# FMC_HPC_UFL_DEBUG_J85_J156.net
KiCad netlist of a schematic drawn in Altium Designer
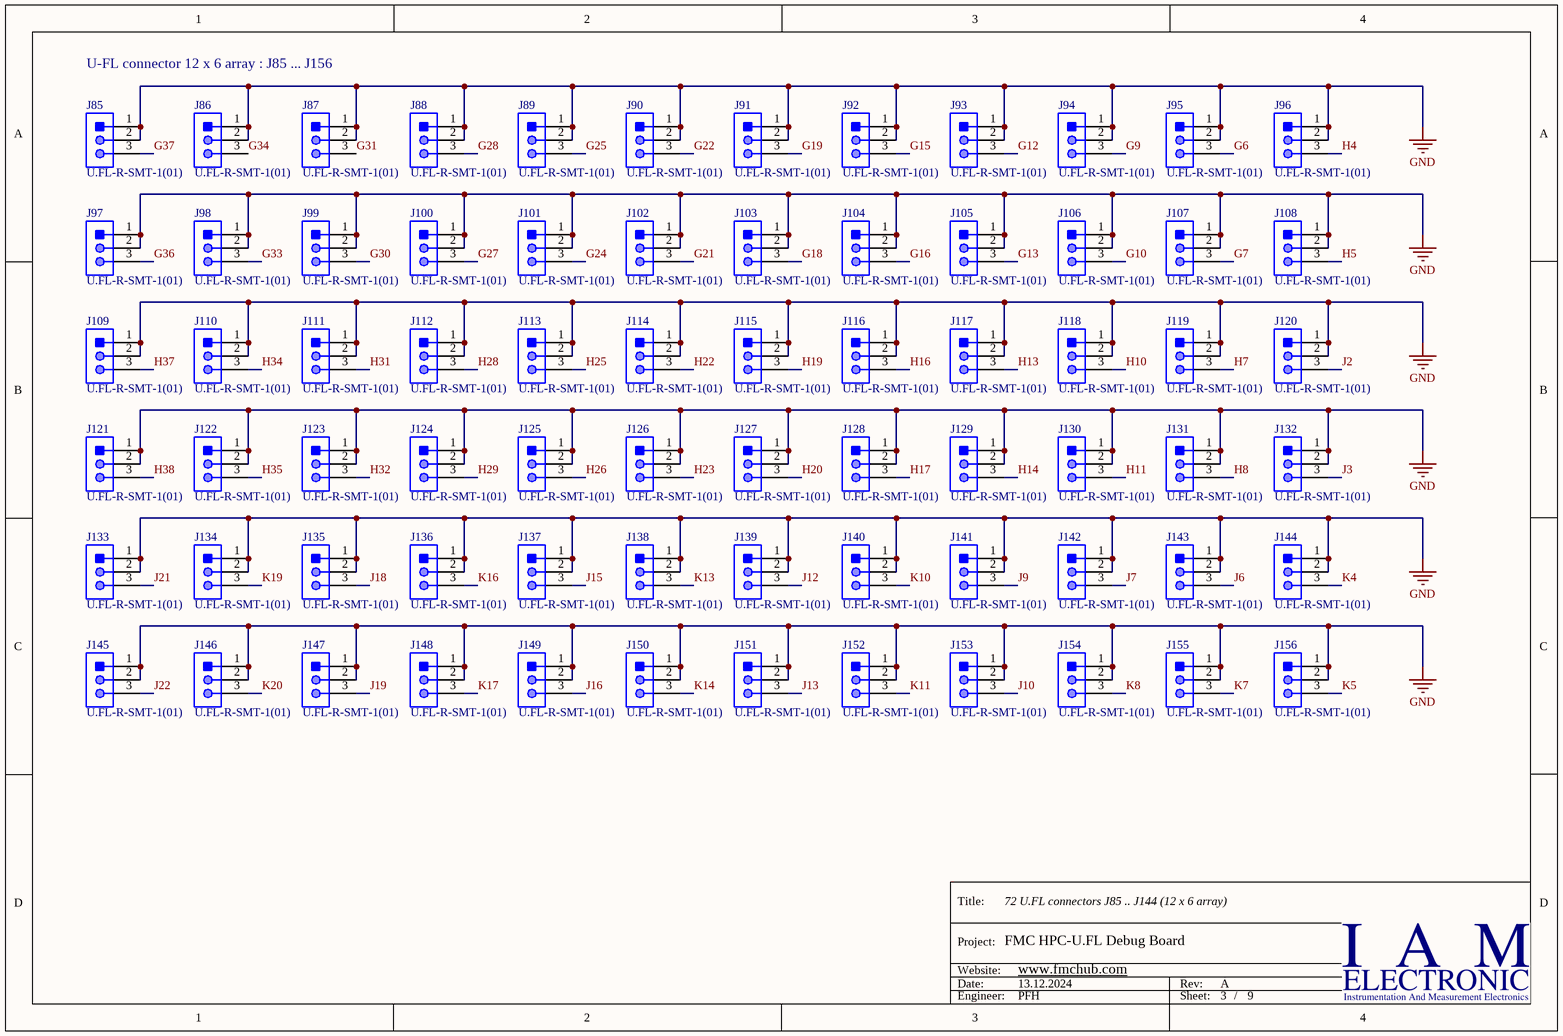
[diagram p0: FMC_HPC_UFL_DEBUG_J85_J156.SchDoc]

(export (version "E")
  (design (tool "Eeschema 10.0.6"))
  (components
    (comp (ref "J85")
      (value "U.FL-R-SMT-1(01)")
      (footprint "HRS-U.FL-R-SMT-3_V")
      (description "Ultra Small Coaxial Connector, 6 GHz, -40 to 90 degC, 3-Pin SMD, RoHS, Bulk")
      (fields (field (name "MANUFACTURER") "Hirose Electric"))
      (libsource (lib "Altium Content Vault") (part "CN-1P-M-R3"))
    )
    (comp (ref "J86")
      (value "U.FL-R-SMT-1(01)")
      (footprint "HRS-U.FL-R-SMT-3_V")
      (description "Ultra Small Coaxial Connector, 6 GHz, -40 to 90 degC, 3-Pin SMD, RoHS, Bulk")
      (fields (field (name "MANUFACTURER") "Hirose Electric"))
      (libsource (lib "Altium Content Vault") (part "CN-1P-M-R3"))
    )
    (comp (ref "J87")
      (value "U.FL-R-SMT-1(01)")
      (footprint "HRS-U.FL-R-SMT-3_V")
      (description "Ultra Small Coaxial Connector, 6 GHz, -40 to 90 degC, 3-Pin SMD, RoHS, Bulk")
      (fields (field (name "MANUFACTURER") "Hirose Electric"))
      (libsource (lib "Altium Content Vault") (part "CN-1P-M-R3"))
    )
    (comp (ref "J88")
      (value "U.FL-R-SMT-1(01)")
      (footprint "HRS-U.FL-R-SMT-3_V")
      (description "Ultra Small Coaxial Connector, 6 GHz, -40 to 90 degC, 3-Pin SMD, RoHS, Bulk")
      (fields (field (name "MANUFACTURER") "Hirose Electric"))
      (libsource (lib "Altium Content Vault") (part "CN-1P-M-R3"))
    )
    (comp (ref "J89")
      (value "U.FL-R-SMT-1(01)")
      (footprint "HRS-U.FL-R-SMT-3_V")
      (description "Ultra Small Coaxial Connector, 6 GHz, -40 to 90 degC, 3-Pin SMD, RoHS, Bulk")
      (fields (field (name "MANUFACTURER") "Hirose Electric"))
      (libsource (lib "Altium Content Vault") (part "CN-1P-M-R3"))
    )
    (comp (ref "J90")
      (value "U.FL-R-SMT-1(01)")
      (footprint "HRS-U.FL-R-SMT-3_V")
      (description "Ultra Small Coaxial Connector, 6 GHz, -40 to 90 degC, 3-Pin SMD, RoHS, Bulk")
      (fields (field (name "MANUFACTURER") "Hirose Electric"))
      (libsource (lib "Altium Content Vault") (part "CN-1P-M-R3"))
    )
    (comp (ref "J91")
      (value "U.FL-R-SMT-1(01)")
      (footprint "HRS-U.FL-R-SMT-3_V")
      (description "Ultra Small Coaxial Connector, 6 GHz, -40 to 90 degC, 3-Pin SMD, RoHS, Bulk")
      (fields (field (name "MANUFACTURER") "Hirose Electric"))
      (libsource (lib "Altium Content Vault") (part "CN-1P-M-R3"))
    )
    (comp (ref "J92")
      (value "U.FL-R-SMT-1(01)")
      (footprint "HRS-U.FL-R-SMT-3_V")
      (description "Ultra Small Coaxial Connector, 6 GHz, -40 to 90 degC, 3-Pin SMD, RoHS, Bulk")
      (fields (field (name "MANUFACTURER") "Hirose Electric"))
      (libsource (lib "Altium Content Vault") (part "CN-1P-M-R3"))
    )
    (comp (ref "J93")
      (value "U.FL-R-SMT-1(01)")
      (footprint "HRS-U.FL-R-SMT-3_V")
      (description "Ultra Small Coaxial Connector, 6 GHz, -40 to 90 degC, 3-Pin SMD, RoHS, Bulk")
      (fields (field (name "MANUFACTURER") "Hirose Electric"))
      (libsource (lib "Altium Content Vault") (part "CN-1P-M-R3"))
    )
    (comp (ref "J94")
      (value "U.FL-R-SMT-1(01)")
      (footprint "HRS-U.FL-R-SMT-3_V")
      (description "Ultra Small Coaxial Connector, 6 GHz, -40 to 90 degC, 3-Pin SMD, RoHS, Bulk")
      (fields (field (name "MANUFACTURER") "Hirose Electric"))
      (libsource (lib "Altium Content Vault") (part "CN-1P-M-R3"))
    )
    (comp (ref "J95")
      (value "U.FL-R-SMT-1(01)")
      (footprint "HRS-U.FL-R-SMT-3_V")
      (description "Ultra Small Coaxial Connector, 6 GHz, -40 to 90 degC, 3-Pin SMD, RoHS, Bulk")
      (fields (field (name "MANUFACTURER") "Hirose Electric"))
      (libsource (lib "Altium Content Vault") (part "CN-1P-M-R3"))
    )
    (comp (ref "J96")
      (value "U.FL-R-SMT-1(01)")
      (footprint "HRS-U.FL-R-SMT-3_V")
      (description "Ultra Small Coaxial Connector, 6 GHz, -40 to 90 degC, 3-Pin SMD, RoHS, Bulk")
      (fields (field (name "MANUFACTURER") "Hirose Electric"))
      (libsource (lib "Altium Content Vault") (part "CN-1P-M-R3"))
    )
    (comp (ref "J97")
      (value "U.FL-R-SMT-1(01)")
      (footprint "HRS-U.FL-R-SMT-3_V")
      (description "Ultra Small Coaxial Connector, 6 GHz, -40 to 90 degC, 3-Pin SMD, RoHS, Bulk")
      (fields (field (name "MANUFACTURER") "Hirose Electric"))
      (libsource (lib "Altium Content Vault") (part "CN-1P-M-R3"))
    )
    (comp (ref "J98")
      (value "U.FL-R-SMT-1(01)")
      (footprint "HRS-U.FL-R-SMT-3_V")
      (description "Ultra Small Coaxial Connector, 6 GHz, -40 to 90 degC, 3-Pin SMD, RoHS, Bulk")
      (fields (field (name "MANUFACTURER") "Hirose Electric"))
      (libsource (lib "Altium Content Vault") (part "CN-1P-M-R3"))
    )
    (comp (ref "J99")
      (value "U.FL-R-SMT-1(01)")
      (footprint "HRS-U.FL-R-SMT-3_V")
      (description "Ultra Small Coaxial Connector, 6 GHz, -40 to 90 degC, 3-Pin SMD, RoHS, Bulk")
      (fields (field (name "MANUFACTURER") "Hirose Electric"))
      (libsource (lib "Altium Content Vault") (part "CN-1P-M-R3"))
    )
    (comp (ref "J100")
      (value "U.FL-R-SMT-1(01)")
      (footprint "HRS-U.FL-R-SMT-3_V")
      (description "Ultra Small Coaxial Connector, 6 GHz, -40 to 90 degC, 3-Pin SMD, RoHS, Bulk")
      (fields (field (name "MANUFACTURER") "Hirose Electric"))
      (libsource (lib "Altium Content Vault") (part "CN-1P-M-R3"))
    )
    (comp (ref "J101")
      (value "U.FL-R-SMT-1(01)")
      (footprint "HRS-U.FL-R-SMT-3_V")
      (description "Ultra Small Coaxial Connector, 6 GHz, -40 to 90 degC, 3-Pin SMD, RoHS, Bulk")
      (fields (field (name "MANUFACTURER") "Hirose Electric"))
      (libsource (lib "Altium Content Vault") (part "CN-1P-M-R3"))
    )
    (comp (ref "J102")
      (value "U.FL-R-SMT-1(01)")
      (footprint "HRS-U.FL-R-SMT-3_V")
      (description "Ultra Small Coaxial Connector, 6 GHz, -40 to 90 degC, 3-Pin SMD, RoHS, Bulk")
      (fields (field (name "MANUFACTURER") "Hirose Electric"))
      (libsource (lib "Altium Content Vault") (part "CN-1P-M-R3"))
    )
    (comp (ref "J103")
      (value "U.FL-R-SMT-1(01)")
      (footprint "HRS-U.FL-R-SMT-3_V")
      (description "Ultra Small Coaxial Connector, 6 GHz, -40 to 90 degC, 3-Pin SMD, RoHS, Bulk")
      (fields (field (name "MANUFACTURER") "Hirose Electric"))
      (libsource (lib "Altium Content Vault") (part "CN-1P-M-R3"))
    )
    (comp (ref "J104")
      (value "U.FL-R-SMT-1(01)")
      (footprint "HRS-U.FL-R-SMT-3_V")
      (description "Ultra Small Coaxial Connector, 6 GHz, -40 to 90 degC, 3-Pin SMD, RoHS, Bulk")
      (fields (field (name "MANUFACTURER") "Hirose Electric"))
      (libsource (lib "Altium Content Vault") (part "CN-1P-M-R3"))
    )
    (comp (ref "J105")
      (value "U.FL-R-SMT-1(01)")
      (footprint "HRS-U.FL-R-SMT-3_V")
      (description "Ultra Small Coaxial Connector, 6 GHz, -40 to 90 degC, 3-Pin SMD, RoHS, Bulk")
      (fields (field (name "MANUFACTURER") "Hirose Electric"))
      (libsource (lib "Altium Content Vault") (part "CN-1P-M-R3"))
    )
    (comp (ref "J106")
      (value "U.FL-R-SMT-1(01)")
      (footprint "HRS-U.FL-R-SMT-3_V")
      (description "Ultra Small Coaxial Connector, 6 GHz, -40 to 90 degC, 3-Pin SMD, RoHS, Bulk")
      (fields (field (name "MANUFACTURER") "Hirose Electric"))
      (libsource (lib "Altium Content Vault") (part "CN-1P-M-R3"))
    )
    (comp (ref "J107")
      (value "U.FL-R-SMT-1(01)")
      (footprint "HRS-U.FL-R-SMT-3_V")
      (description "Ultra Small Coaxial Connector, 6 GHz, -40 to 90 degC, 3-Pin SMD, RoHS, Bulk")
      (fields (field (name "MANUFACTURER") "Hirose Electric"))
      (libsource (lib "Altium Content Vault") (part "CN-1P-M-R3"))
    )
    (comp (ref "J108")
      (value "U.FL-R-SMT-1(01)")
      (footprint "HRS-U.FL-R-SMT-3_V")
      (description "Ultra Small Coaxial Connector, 6 GHz, -40 to 90 degC, 3-Pin SMD, RoHS, Bulk")
      (fields (field (name "MANUFACTURER") "Hirose Electric"))
      (libsource (lib "Altium Content Vault") (part "CN-1P-M-R3"))
    )
    (comp (ref "J109")
      (value "U.FL-R-SMT-1(01)")
      (footprint "HRS-U.FL-R-SMT-3_V")
      (description "Ultra Small Coaxial Connector, 6 GHz, -40 to 90 degC, 3-Pin SMD, RoHS, Bulk")
      (fields (field (name "MANUFACTURER") "Hirose Electric"))
      (libsource (lib "Altium Content Vault") (part "CN-1P-M-R3"))
    )
    (comp (ref "J110")
      (value "U.FL-R-SMT-1(01)")
      (footprint "HRS-U.FL-R-SMT-3_V")
      (description "Ultra Small Coaxial Connector, 6 GHz, -40 to 90 degC, 3-Pin SMD, RoHS, Bulk")
      (fields (field (name "MANUFACTURER") "Hirose Electric"))
      (libsource (lib "Altium Content Vault") (part "CN-1P-M-R3"))
    )
    (comp (ref "J111")
      (value "U.FL-R-SMT-1(01)")
      (footprint "HRS-U.FL-R-SMT-3_V")
      (description "Ultra Small Coaxial Connector, 6 GHz, -40 to 90 degC, 3-Pin SMD, RoHS, Bulk")
      (fields (field (name "MANUFACTURER") "Hirose Electric"))
      (libsource (lib "Altium Content Vault") (part "CN-1P-M-R3"))
    )
    (comp (ref "J112")
      (value "U.FL-R-SMT-1(01)")
      (footprint "HRS-U.FL-R-SMT-3_V")
      (description "Ultra Small Coaxial Connector, 6 GHz, -40 to 90 degC, 3-Pin SMD, RoHS, Bulk")
      (fields (field (name "MANUFACTURER") "Hirose Electric"))
      (libsource (lib "Altium Content Vault") (part "CN-1P-M-R3"))
    )
    (comp (ref "J113")
      (value "U.FL-R-SMT-1(01)")
      (footprint "HRS-U.FL-R-SMT-3_V")
      (description "Ultra Small Coaxial Connector, 6 GHz, -40 to 90 degC, 3-Pin SMD, RoHS, Bulk")
      (fields (field (name "MANUFACTURER") "Hirose Electric"))
      (libsource (lib "Altium Content Vault") (part "CN-1P-M-R3"))
    )
    (comp (ref "J114")
      (value "U.FL-R-SMT-1(01)")
      (footprint "HRS-U.FL-R-SMT-3_V")
      (description "Ultra Small Coaxial Connector, 6 GHz, -40 to 90 degC, 3-Pin SMD, RoHS, Bulk")
      (fields (field (name "MANUFACTURER") "Hirose Electric"))
      (libsource (lib "Altium Content Vault") (part "CN-1P-M-R3"))
    )
    (comp (ref "J115")
      (value "U.FL-R-SMT-1(01)")
      (footprint "HRS-U.FL-R-SMT-3_V")
      (description "Ultra Small Coaxial Connector, 6 GHz, -40 to 90 degC, 3-Pin SMD, RoHS, Bulk")
      (fields (field (name "MANUFACTURER") "Hirose Electric"))
      (libsource (lib "Altium Content Vault") (part "CN-1P-M-R3"))
    )
    (comp (ref "J116")
      (value "U.FL-R-SMT-1(01)")
      (footprint "HRS-U.FL-R-SMT-3_V")
      (description "Ultra Small Coaxial Connector, 6 GHz, -40 to 90 degC, 3-Pin SMD, RoHS, Bulk")
      (fields (field (name "MANUFACTURER") "Hirose Electric"))
      (libsource (lib "Altium Content Vault") (part "CN-1P-M-R3"))
    )
    (comp (ref "J117")
      (value "U.FL-R-SMT-1(01)")
      (footprint "HRS-U.FL-R-SMT-3_V")
      (description "Ultra Small Coaxial Connector, 6 GHz, -40 to 90 degC, 3-Pin SMD, RoHS, Bulk")
      (fields (field (name "MANUFACTURER") "Hirose Electric"))
      (libsource (lib "Altium Content Vault") (part "CN-1P-M-R3"))
    )
    (comp (ref "J118")
      (value "U.FL-R-SMT-1(01)")
      (footprint "HRS-U.FL-R-SMT-3_V")
      (description "Ultra Small Coaxial Connector, 6 GHz, -40 to 90 degC, 3-Pin SMD, RoHS, Bulk")
      (fields (field (name "MANUFACTURER") "Hirose Electric"))
      (libsource (lib "Altium Content Vault") (part "CN-1P-M-R3"))
    )
    (comp (ref "J119")
      (value "U.FL-R-SMT-1(01)")
      (footprint "HRS-U.FL-R-SMT-3_V")
      (description "Ultra Small Coaxial Connector, 6 GHz, -40 to 90 degC, 3-Pin SMD, RoHS, Bulk")
      (fields (field (name "MANUFACTURER") "Hirose Electric"))
      (libsource (lib "Altium Content Vault") (part "CN-1P-M-R3"))
    )
    (comp (ref "J120")
      (value "U.FL-R-SMT-1(01)")
      (footprint "HRS-U.FL-R-SMT-3_V")
      (description "Ultra Small Coaxial Connector, 6 GHz, -40 to 90 degC, 3-Pin SMD, RoHS, Bulk")
      (fields (field (name "MANUFACTURER") "Hirose Electric"))
      (libsource (lib "Altium Content Vault") (part "CN-1P-M-R3"))
    )
    (comp (ref "J121")
      (value "U.FL-R-SMT-1(01)")
      (footprint "HRS-U.FL-R-SMT-3_V")
      (description "Ultra Small Coaxial Connector, 6 GHz, -40 to 90 degC, 3-Pin SMD, RoHS, Bulk")
      (fields (field (name "MANUFACTURER") "Hirose Electric"))
      (libsource (lib "Altium Content Vault") (part "CN-1P-M-R3"))
    )
    (comp (ref "J122")
      (value "U.FL-R-SMT-1(01)")
      (footprint "HRS-U.FL-R-SMT-3_V")
      (description "Ultra Small Coaxial Connector, 6 GHz, -40 to 90 degC, 3-Pin SMD, RoHS, Bulk")
      (fields (field (name "MANUFACTURER") "Hirose Electric"))
      (libsource (lib "Altium Content Vault") (part "CN-1P-M-R3"))
    )
    (comp (ref "J123")
      (value "U.FL-R-SMT-1(01)")
      (footprint "HRS-U.FL-R-SMT-3_V")
      (description "Ultra Small Coaxial Connector, 6 GHz, -40 to 90 degC, 3-Pin SMD, RoHS, Bulk")
      (fields (field (name "MANUFACTURER") "Hirose Electric"))
      (libsource (lib "Altium Content Vault") (part "CN-1P-M-R3"))
    )
    (comp (ref "J124")
      (value "U.FL-R-SMT-1(01)")
      (footprint "HRS-U.FL-R-SMT-3_V")
      (description "Ultra Small Coaxial Connector, 6 GHz, -40 to 90 degC, 3-Pin SMD, RoHS, Bulk")
      (fields (field (name "MANUFACTURER") "Hirose Electric"))
      (libsource (lib "Altium Content Vault") (part "CN-1P-M-R3"))
    )
    (comp (ref "J125")
      (value "U.FL-R-SMT-1(01)")
      (footprint "HRS-U.FL-R-SMT-3_V")
      (description "Ultra Small Coaxial Connector, 6 GHz, -40 to 90 degC, 3-Pin SMD, RoHS, Bulk")
      (fields (field (name "MANUFACTURER") "Hirose Electric"))
      (libsource (lib "Altium Content Vault") (part "CN-1P-M-R3"))
    )
    (comp (ref "J126")
      (value "U.FL-R-SMT-1(01)")
      (footprint "HRS-U.FL-R-SMT-3_V")
      (description "Ultra Small Coaxial Connector, 6 GHz, -40 to 90 degC, 3-Pin SMD, RoHS, Bulk")
      (fields (field (name "MANUFACTURER") "Hirose Electric"))
      (libsource (lib "Altium Content Vault") (part "CN-1P-M-R3"))
    )
    (comp (ref "J127")
      (value "U.FL-R-SMT-1(01)")
      (footprint "HRS-U.FL-R-SMT-3_V")
      (description "Ultra Small Coaxial Connector, 6 GHz, -40 to 90 degC, 3-Pin SMD, RoHS, Bulk")
      (fields (field (name "MANUFACTURER") "Hirose Electric"))
      (libsource (lib "Altium Content Vault") (part "CN-1P-M-R3"))
    )
    (comp (ref "J128")
      (value "U.FL-R-SMT-1(01)")
      (footprint "HRS-U.FL-R-SMT-3_V")
      (description "Ultra Small Coaxial Connector, 6 GHz, -40 to 90 degC, 3-Pin SMD, RoHS, Bulk")
      (fields (field (name "MANUFACTURER") "Hirose Electric"))
      (libsource (lib "Altium Content Vault") (part "CN-1P-M-R3"))
    )
    (comp (ref "J129")
      (value "U.FL-R-SMT-1(01)")
      (footprint "HRS-U.FL-R-SMT-3_V")
      (description "Ultra Small Coaxial Connector, 6 GHz, -40 to 90 degC, 3-Pin SMD, RoHS, Bulk")
      (fields (field (name "MANUFACTURER") "Hirose Electric"))
      (libsource (lib "Altium Content Vault") (part "CN-1P-M-R3"))
    )
    (comp (ref "J130")
      (value "U.FL-R-SMT-1(01)")
      (footprint "HRS-U.FL-R-SMT-3_V")
      (description "Ultra Small Coaxial Connector, 6 GHz, -40 to 90 degC, 3-Pin SMD, RoHS, Bulk")
      (fields (field (name "MANUFACTURER") "Hirose Electric"))
      (libsource (lib "Altium Content Vault") (part "CN-1P-M-R3"))
    )
    (comp (ref "J131")
      (value "U.FL-R-SMT-1(01)")
      (footprint "HRS-U.FL-R-SMT-3_V")
      (description "Ultra Small Coaxial Connector, 6 GHz, -40 to 90 degC, 3-Pin SMD, RoHS, Bulk")
      (fields (field (name "MANUFACTURER") "Hirose Electric"))
      (libsource (lib "Altium Content Vault") (part "CN-1P-M-R3"))
    )
    (comp (ref "J132")
      (value "U.FL-R-SMT-1(01)")
      (footprint "HRS-U.FL-R-SMT-3_V")
      (description "Ultra Small Coaxial Connector, 6 GHz, -40 to 90 degC, 3-Pin SMD, RoHS, Bulk")
      (fields (field (name "MANUFACTURER") "Hirose Electric"))
      (libsource (lib "Altium Content Vault") (part "CN-1P-M-R3"))
    )
    (comp (ref "J133")
      (value "U.FL-R-SMT-1(01)")
      (footprint "HRS-U.FL-R-SMT-3_V")
      (description "Ultra Small Coaxial Connector, 6 GHz, -40 to 90 degC, 3-Pin SMD, RoHS, Bulk")
      (fields (field (name "MANUFACTURER") "Hirose Electric"))
      (libsource (lib "Altium Content Vault") (part "CN-1P-M-R3"))
    )
    (comp (ref "J134")
      (value "U.FL-R-SMT-1(01)")
      (footprint "HRS-U.FL-R-SMT-3_V")
      (description "Ultra Small Coaxial Connector, 6 GHz, -40 to 90 degC, 3-Pin SMD, RoHS, Bulk")
      (fields (field (name "MANUFACTURER") "Hirose Electric"))
      (libsource (lib "Altium Content Vault") (part "CN-1P-M-R3"))
    )
    (comp (ref "J135")
      (value "U.FL-R-SMT-1(01)")
      (footprint "HRS-U.FL-R-SMT-3_V")
      (description "Ultra Small Coaxial Connector, 6 GHz, -40 to 90 degC, 3-Pin SMD, RoHS, Bulk")
      (fields (field (name "MANUFACTURER") "Hirose Electric"))
      (libsource (lib "Altium Content Vault") (part "CN-1P-M-R3"))
    )
    (comp (ref "J136")
      (value "U.FL-R-SMT-1(01)")
      (footprint "HRS-U.FL-R-SMT-3_V")
      (description "Ultra Small Coaxial Connector, 6 GHz, -40 to 90 degC, 3-Pin SMD, RoHS, Bulk")
      (fields (field (name "MANUFACTURER") "Hirose Electric"))
      (libsource (lib "Altium Content Vault") (part "CN-1P-M-R3"))
    )
    (comp (ref "J137")
      (value "U.FL-R-SMT-1(01)")
      (footprint "HRS-U.FL-R-SMT-3_V")
      (description "Ultra Small Coaxial Connector, 6 GHz, -40 to 90 degC, 3-Pin SMD, RoHS, Bulk")
      (fields (field (name "MANUFACTURER") "Hirose Electric"))
      (libsource (lib "Altium Content Vault") (part "CN-1P-M-R3"))
    )
    (comp (ref "J138")
      (value "U.FL-R-SMT-1(01)")
      (footprint "HRS-U.FL-R-SMT-3_V")
      (description "Ultra Small Coaxial Connector, 6 GHz, -40 to 90 degC, 3-Pin SMD, RoHS, Bulk")
      (fields (field (name "MANUFACTURER") "Hirose Electric"))
      (libsource (lib "Altium Content Vault") (part "CN-1P-M-R3"))
    )
    (comp (ref "J139")
      (value "U.FL-R-SMT-1(01)")
      (footprint "HRS-U.FL-R-SMT-3_V")
      (description "Ultra Small Coaxial Connector, 6 GHz, -40 to 90 degC, 3-Pin SMD, RoHS, Bulk")
      (fields (field (name "MANUFACTURER") "Hirose Electric"))
      (libsource (lib "Altium Content Vault") (part "CN-1P-M-R3"))
    )
    (comp (ref "J140")
      (value "U.FL-R-SMT-1(01)")
      (footprint "HRS-U.FL-R-SMT-3_V")
      (description "Ultra Small Coaxial Connector, 6 GHz, -40 to 90 degC, 3-Pin SMD, RoHS, Bulk")
      (fields (field (name "MANUFACTURER") "Hirose Electric"))
      (libsource (lib "Altium Content Vault") (part "CN-1P-M-R3"))
    )
    (comp (ref "J141")
      (value "U.FL-R-SMT-1(01)")
      (footprint "HRS-U.FL-R-SMT-3_V")
      (description "Ultra Small Coaxial Connector, 6 GHz, -40 to 90 degC, 3-Pin SMD, RoHS, Bulk")
      (fields (field (name "MANUFACTURER") "Hirose Electric"))
      (libsource (lib "Altium Content Vault") (part "CN-1P-M-R3"))
    )
    (comp (ref "J142")
      (value "U.FL-R-SMT-1(01)")
      (footprint "HRS-U.FL-R-SMT-3_V")
      (description "Ultra Small Coaxial Connector, 6 GHz, -40 to 90 degC, 3-Pin SMD, RoHS, Bulk")
      (fields (field (name "MANUFACTURER") "Hirose Electric"))
      (libsource (lib "Altium Content Vault") (part "CN-1P-M-R3"))
    )
    (comp (ref "J143")
      (value "U.FL-R-SMT-1(01)")
      (footprint "HRS-U.FL-R-SMT-3_V")
      (description "Ultra Small Coaxial Connector, 6 GHz, -40 to 90 degC, 3-Pin SMD, RoHS, Bulk")
      (fields (field (name "MANUFACTURER") "Hirose Electric"))
      (libsource (lib "Altium Content Vault") (part "CN-1P-M-R3"))
    )
    (comp (ref "J144")
      (value "U.FL-R-SMT-1(01)")
      (footprint "HRS-U.FL-R-SMT-3_V")
      (description "Ultra Small Coaxial Connector, 6 GHz, -40 to 90 degC, 3-Pin SMD, RoHS, Bulk")
      (fields (field (name "MANUFACTURER") "Hirose Electric"))
      (libsource (lib "Altium Content Vault") (part "CN-1P-M-R3"))
    )
    (comp (ref "J145")
      (value "U.FL-R-SMT-1(01)")
      (footprint "HRS-U.FL-R-SMT-3_V")
      (description "Ultra Small Coaxial Connector, 6 GHz, -40 to 90 degC, 3-Pin SMD, RoHS, Bulk")
      (fields (field (name "MANUFACTURER") "Hirose Electric"))
      (libsource (lib "Altium Content Vault") (part "CN-1P-M-R3"))
    )
    (comp (ref "J146")
      (value "U.FL-R-SMT-1(01)")
      (footprint "HRS-U.FL-R-SMT-3_V")
      (description "Ultra Small Coaxial Connector, 6 GHz, -40 to 90 degC, 3-Pin SMD, RoHS, Bulk")
      (fields (field (name "MANUFACTURER") "Hirose Electric"))
      (libsource (lib "Altium Content Vault") (part "CN-1P-M-R3"))
    )
    (comp (ref "J147")
      (value "U.FL-R-SMT-1(01)")
      (footprint "HRS-U.FL-R-SMT-3_V")
      (description "Ultra Small Coaxial Connector, 6 GHz, -40 to 90 degC, 3-Pin SMD, RoHS, Bulk")
      (fields (field (name "MANUFACTURER") "Hirose Electric"))
      (libsource (lib "Altium Content Vault") (part "CN-1P-M-R3"))
    )
    (comp (ref "J148")
      (value "U.FL-R-SMT-1(01)")
      (footprint "HRS-U.FL-R-SMT-3_V")
      (description "Ultra Small Coaxial Connector, 6 GHz, -40 to 90 degC, 3-Pin SMD, RoHS, Bulk")
      (fields (field (name "MANUFACTURER") "Hirose Electric"))
      (libsource (lib "Altium Content Vault") (part "CN-1P-M-R3"))
    )
    (comp (ref "J149")
      (value "U.FL-R-SMT-1(01)")
      (footprint "HRS-U.FL-R-SMT-3_V")
      (description "Ultra Small Coaxial Connector, 6 GHz, -40 to 90 degC, 3-Pin SMD, RoHS, Bulk")
      (fields (field (name "MANUFACTURER") "Hirose Electric"))
      (libsource (lib "Altium Content Vault") (part "CN-1P-M-R3"))
    )
    (comp (ref "J150")
      (value "U.FL-R-SMT-1(01)")
      (footprint "HRS-U.FL-R-SMT-3_V")
      (description "Ultra Small Coaxial Connector, 6 GHz, -40 to 90 degC, 3-Pin SMD, RoHS, Bulk")
      (fields (field (name "MANUFACTURER") "Hirose Electric"))
      (libsource (lib "Altium Content Vault") (part "CN-1P-M-R3"))
    )
    (comp (ref "J151")
      (value "U.FL-R-SMT-1(01)")
      (footprint "HRS-U.FL-R-SMT-3_V")
      (description "Ultra Small Coaxial Connector, 6 GHz, -40 to 90 degC, 3-Pin SMD, RoHS, Bulk")
      (fields (field (name "MANUFACTURER") "Hirose Electric"))
      (libsource (lib "Altium Content Vault") (part "CN-1P-M-R3"))
    )
    (comp (ref "J152")
      (value "U.FL-R-SMT-1(01)")
      (footprint "HRS-U.FL-R-SMT-3_V")
      (description "Ultra Small Coaxial Connector, 6 GHz, -40 to 90 degC, 3-Pin SMD, RoHS, Bulk")
      (fields (field (name "MANUFACTURER") "Hirose Electric"))
      (libsource (lib "Altium Content Vault") (part "CN-1P-M-R3"))
    )
    (comp (ref "J153")
      (value "U.FL-R-SMT-1(01)")
      (footprint "HRS-U.FL-R-SMT-3_V")
      (description "Ultra Small Coaxial Connector, 6 GHz, -40 to 90 degC, 3-Pin SMD, RoHS, Bulk")
      (fields (field (name "MANUFACTURER") "Hirose Electric"))
      (libsource (lib "Altium Content Vault") (part "CN-1P-M-R3"))
    )
    (comp (ref "J154")
      (value "U.FL-R-SMT-1(01)")
      (footprint "HRS-U.FL-R-SMT-3_V")
      (description "Ultra Small Coaxial Connector, 6 GHz, -40 to 90 degC, 3-Pin SMD, RoHS, Bulk")
      (fields (field (name "MANUFACTURER") "Hirose Electric"))
      (libsource (lib "Altium Content Vault") (part "CN-1P-M-R3"))
    )
    (comp (ref "J155")
      (value "U.FL-R-SMT-1(01)")
      (footprint "HRS-U.FL-R-SMT-3_V")
      (description "Ultra Small Coaxial Connector, 6 GHz, -40 to 90 degC, 3-Pin SMD, RoHS, Bulk")
      (fields (field (name "MANUFACTURER") "Hirose Electric"))
      (libsource (lib "Altium Content Vault") (part "CN-1P-M-R3"))
    )
    (comp (ref "J156")
      (value "U.FL-R-SMT-1(01)")
      (footprint "HRS-U.FL-R-SMT-3_V")
      (description "Ultra Small Coaxial Connector, 6 GHz, -40 to 90 degC, 3-Pin SMD, RoHS, Bulk")
      (fields (field (name "MANUFACTURER") "Hirose Electric"))
      (libsource (lib "Altium Content Vault") (part "CN-1P-M-R3"))
    )
  )
  (nets
    (net (code "1") (name "/G6") (class "Default")
      (node (ref "J95") (pin "3") (pinfunction "3_3") (pintype "passive"))
    )
    (net (code "2") (name "/G7") (class "Default")
      (node (ref "J107") (pin "3") (pinfunction "3_3") (pintype "passive"))
    )
    (net (code "3") (name "/G9") (class "Default")
      (node (ref "J94") (pin "3") (pinfunction "3_3") (pintype "passive"))
    )
    (net (code "4") (name "/G10") (class "Default")
      (node (ref "J106") (pin "3") (pinfunction "3_3") (pintype "passive"))
    )
    (net (code "5") (name "/G12") (class "Default")
      (node (ref "J93") (pin "3") (pinfunction "3_3") (pintype "passive"))
    )
    (net (code "6") (name "/G13") (class "Default")
      (node (ref "J105") (pin "3") (pinfunction "3_3") (pintype "passive"))
    )
    (net (code "7") (name "/G15") (class "Default")
      (node (ref "J92") (pin "3") (pinfunction "3_3") (pintype "passive"))
    )
    (net (code "8") (name "/G16") (class "Default")
      (node (ref "J104") (pin "3") (pinfunction "3_3") (pintype "passive"))
    )
    (net (code "9") (name "/G18") (class "Default")
      (node (ref "J103") (pin "3") (pinfunction "3_3") (pintype "passive"))
    )
    (net (code "10") (name "/G19") (class "Default")
      (node (ref "J91") (pin "3") (pinfunction "3_3") (pintype "passive"))
    )
    (net (code "11") (name "/G21") (class "Default")
      (node (ref "J102") (pin "3") (pinfunction "3_3") (pintype "passive"))
    )
    (net (code "12") (name "/G22") (class "Default")
      (node (ref "J90") (pin "3") (pinfunction "3_3") (pintype "passive"))
    )
    (net (code "13") (name "/G24") (class "Default")
      (node (ref "J101") (pin "3") (pinfunction "3_3") (pintype "passive"))
    )
    (net (code "14") (name "/G25") (class "Default")
      (node (ref "J89") (pin "3") (pinfunction "3_3") (pintype "passive"))
    )
    (net (code "15") (name "/G27") (class "Default")
      (node (ref "J100") (pin "3") (pinfunction "3_3") (pintype "passive"))
    )
    (net (code "16") (name "/G28") (class "Default")
      (node (ref "J88") (pin "3") (pinfunction "3_3") (pintype "passive"))
    )
    (net (code "17") (name "/G30") (class "Default")
      (node (ref "J99") (pin "3") (pinfunction "3_3") (pintype "passive"))
    )
    (net (code "18") (name "/G31") (class "Default")
      (node (ref "J87") (pin "3") (pinfunction "3_3") (pintype "passive"))
    )
    (net (code "19") (name "/G33") (class "Default")
      (node (ref "J98") (pin "3") (pinfunction "3_3") (pintype "passive"))
    )
    (net (code "20") (name "/G34") (class "Default")
      (node (ref "J86") (pin "3") (pinfunction "3_3") (pintype "passive"))
    )
    (net (code "21") (name "/G36") (class "Default")
      (node (ref "J97") (pin "3") (pinfunction "3_3") (pintype "passive"))
    )
    (net (code "22") (name "/G37") (class "Default")
      (node (ref "J85") (pin "3") (pinfunction "3_3") (pintype "passive"))
    )
    (net (code "23") (name "/H4") (class "Default")
      (node (ref "J96") (pin "3") (pinfunction "3_3") (pintype "passive"))
    )
    (net (code "24") (name "/H5") (class "Default")
      (node (ref "J108") (pin "3") (pinfunction "3_3") (pintype "passive"))
    )
    (net (code "25") (name "/H7") (class "Default")
      (node (ref "J119") (pin "3") (pinfunction "3_3") (pintype "passive"))
    )
    (net (code "26") (name "/H8") (class "Default")
      (node (ref "J131") (pin "3") (pinfunction "3_3") (pintype "passive"))
    )
    (net (code "27") (name "/H10") (class "Default")
      (node (ref "J118") (pin "3") (pinfunction "3_3") (pintype "passive"))
    )
    (net (code "28") (name "/H11") (class "Default")
      (node (ref "J130") (pin "3") (pinfunction "3_3") (pintype "passive"))
    )
    (net (code "29") (name "/H13") (class "Default")
      (node (ref "J117") (pin "3") (pinfunction "3_3") (pintype "passive"))
    )
    (net (code "30") (name "/H14") (class "Default")
      (node (ref "J129") (pin "3") (pinfunction "3_3") (pintype "passive"))
    )
    (net (code "31") (name "/H16") (class "Default")
      (node (ref "J116") (pin "3") (pinfunction "3_3") (pintype "passive"))
    )
    (net (code "32") (name "/H17") (class "Default")
      (node (ref "J128") (pin "3") (pinfunction "3_3") (pintype "passive"))
    )
    (net (code "33") (name "/H19") (class "Default")
      (node (ref "J115") (pin "3") (pinfunction "3_3") (pintype "passive"))
    )
    (net (code "34") (name "/H20") (class "Default")
      (node (ref "J127") (pin "3") (pinfunction "3_3") (pintype "passive"))
    )
    (net (code "35") (name "/H22") (class "Default")
      (node (ref "J114") (pin "3") (pinfunction "3_3") (pintype "passive"))
    )
    (net (code "36") (name "/H23") (class "Default")
      (node (ref "J126") (pin "3") (pinfunction "3_3") (pintype "passive"))
    )
    (net (code "37") (name "/H25") (class "Default")
      (node (ref "J113") (pin "3") (pinfunction "3_3") (pintype "passive"))
    )
    (net (code "38") (name "/H26") (class "Default")
      (node (ref "J125") (pin "3") (pinfunction "3_3") (pintype "passive"))
    )
    (net (code "39") (name "/H28") (class "Default")
      (node (ref "J112") (pin "3") (pinfunction "3_3") (pintype "passive"))
    )
    (net (code "40") (name "/H29") (class "Default")
      (node (ref "J124") (pin "3") (pinfunction "3_3") (pintype "passive"))
    )
    (net (code "41") (name "/H31") (class "Default")
      (node (ref "J111") (pin "3") (pinfunction "3_3") (pintype "passive"))
    )
    (net (code "42") (name "/H32") (class "Default")
      (node (ref "J123") (pin "3") (pinfunction "3_3") (pintype "passive"))
    )
    (net (code "43") (name "/H34") (class "Default")
      (node (ref "J110") (pin "3") (pinfunction "3_3") (pintype "passive"))
    )
    (net (code "44") (name "/H35") (class "Default")
      (node (ref "J122") (pin "3") (pinfunction "3_3") (pintype "passive"))
    )
    (net (code "45") (name "/H37") (class "Default")
      (node (ref "J109") (pin "3") (pinfunction "3_3") (pintype "passive"))
    )
    (net (code "46") (name "/H38") (class "Default")
      (node (ref "J121") (pin "3") (pinfunction "3_3") (pintype "passive"))
    )
    (net (code "47") (name "/J2") (class "Default")
      (node (ref "J120") (pin "3") (pinfunction "3_3") (pintype "passive"))
    )
    (net (code "48") (name "/J3") (class "Default")
      (node (ref "J132") (pin "3") (pinfunction "3_3") (pintype "passive"))
    )
    (net (code "49") (name "/J6") (class "Default")
      (node (ref "J143") (pin "3") (pinfunction "3_3") (pintype "passive"))
    )
    (net (code "50") (name "/J7") (class "Default")
      (node (ref "J142") (pin "3") (pinfunction "3_3") (pintype "passive"))
    )
    (net (code "51") (name "/J9") (class "Default")
      (node (ref "J141") (pin "3") (pinfunction "3_3") (pintype "passive"))
    )
    (net (code "52") (name "/J10") (class "Default")
      (node (ref "J153") (pin "3") (pinfunction "3_3") (pintype "passive"))
    )
    (net (code "53") (name "/J12") (class "Default")
      (node (ref "J139") (pin "3") (pinfunction "3_3") (pintype "passive"))
    )
    (net (code "54") (name "/J13") (class "Default")
      (node (ref "J151") (pin "3") (pinfunction "3_3") (pintype "passive"))
    )
    (net (code "55") (name "/J15") (class "Default")
      (node (ref "J137") (pin "3") (pinfunction "3_3") (pintype "passive"))
    )
    (net (code "56") (name "/J16") (class "Default")
      (node (ref "J149") (pin "3") (pinfunction "3_3") (pintype "passive"))
    )
    (net (code "57") (name "/J18") (class "Default")
      (node (ref "J135") (pin "3") (pinfunction "3_3") (pintype "passive"))
    )
    (net (code "58") (name "/J19") (class "Default")
      (node (ref "J147") (pin "3") (pinfunction "3_3") (pintype "passive"))
    )
    (net (code "59") (name "/J21") (class "Default")
      (node (ref "J133") (pin "3") (pinfunction "3_3") (pintype "passive"))
    )
    (net (code "60") (name "/J22") (class "Default")
      (node (ref "J145") (pin "3") (pinfunction "3_3") (pintype "passive"))
    )
    (net (code "61") (name "/K4") (class "Default")
      (node (ref "J144") (pin "3") (pinfunction "3_3") (pintype "passive"))
    )
    (net (code "62") (name "/K5") (class "Default")
      (node (ref "J156") (pin "3") (pinfunction "3_3") (pintype "passive"))
    )
    (net (code "63") (name "/K7") (class "Default")
      (node (ref "J155") (pin "3") (pinfunction "3_3") (pintype "passive"))
    )
    (net (code "64") (name "/K8") (class "Default")
      (node (ref "J154") (pin "3") (pinfunction "3_3") (pintype "passive"))
    )
    (net (code "65") (name "/K10") (class "Default")
      (node (ref "J140") (pin "3") (pinfunction "3_3") (pintype "passive"))
    )
    (net (code "66") (name "/K11") (class "Default")
      (node (ref "J152") (pin "3") (pinfunction "3_3") (pintype "passive"))
    )
    (net (code "67") (name "/K13") (class "Default")
      (node (ref "J138") (pin "3") (pinfunction "3_3") (pintype "passive"))
    )
    (net (code "68") (name "/K14") (class "Default")
      (node (ref "J150") (pin "3") (pinfunction "3_3") (pintype "passive"))
    )
    (net (code "69") (name "/K16") (class "Default")
      (node (ref "J136") (pin "3") (pinfunction "3_3") (pintype "passive"))
    )
    (net (code "70") (name "/K17") (class "Default")
      (node (ref "J148") (pin "3") (pinfunction "3_3") (pintype "passive"))
    )
    (net (code "71") (name "/K19") (class "Default")
      (node (ref "J134") (pin "3") (pinfunction "3_3") (pintype "passive"))
    )
    (net (code "72") (name "/K20") (class "Default")
      (node (ref "J146") (pin "3") (pinfunction "3_3") (pintype "passive"))
    )
    (net (code "73") (name "GND") (class "Default")
      (node (ref "J100") (pin "1") (pinfunction "1_1") (pintype "passive"))
      (node (ref "J100") (pin "2") (pinfunction "2_2") (pintype "passive"))
      (node (ref "J101") (pin "1") (pinfunction "1_1") (pintype "passive"))
      (node (ref "J101") (pin "2") (pinfunction "2_2") (pintype "passive"))
      (node (ref "J102") (pin "1") (pinfunction "1_1") (pintype "passive"))
      (node (ref "J102") (pin "2") (pinfunction "2_2") (pintype "passive"))
      (node (ref "J103") (pin "1") (pinfunction "1_1") (pintype "passive"))
      (node (ref "J103") (pin "2") (pinfunction "2_2") (pintype "passive"))
      (node (ref "J104") (pin "1") (pinfunction "1_1") (pintype "passive"))
      (node (ref "J104") (pin "2") (pinfunction "2_2") (pintype "passive"))
      (node (ref "J105") (pin "1") (pinfunction "1_1") (pintype "passive"))
      (node (ref "J105") (pin "2") (pinfunction "2_2") (pintype "passive"))
      (node (ref "J106") (pin "1") (pinfunction "1_1") (pintype "passive"))
      (node (ref "J106") (pin "2") (pinfunction "2_2") (pintype "passive"))
      (node (ref "J107") (pin "1") (pinfunction "1_1") (pintype "passive"))
      (node (ref "J107") (pin "2") (pinfunction "2_2") (pintype "passive"))
      (node (ref "J108") (pin "1") (pinfunction "1_1") (pintype "passive"))
      (node (ref "J108") (pin "2") (pinfunction "2_2") (pintype "passive"))
      (node (ref "J109") (pin "1") (pinfunction "1_1") (pintype "passive"))
      (node (ref "J109") (pin "2") (pinfunction "2_2") (pintype "passive"))
      (node (ref "J110") (pin "1") (pinfunction "1_1") (pintype "passive"))
      (node (ref "J110") (pin "2") (pinfunction "2_2") (pintype "passive"))
      (node (ref "J111") (pin "1") (pinfunction "1_1") (pintype "passive"))
      (node (ref "J111") (pin "2") (pinfunction "2_2") (pintype "passive"))
      (node (ref "J112") (pin "1") (pinfunction "1_1") (pintype "passive"))
      (node (ref "J112") (pin "2") (pinfunction "2_2") (pintype "passive"))
      (node (ref "J113") (pin "1") (pinfunction "1_1") (pintype "passive"))
      (node (ref "J113") (pin "2") (pinfunction "2_2") (pintype "passive"))
      (node (ref "J114") (pin "1") (pinfunction "1_1") (pintype "passive"))
      (node (ref "J114") (pin "2") (pinfunction "2_2") (pintype "passive"))
      (node (ref "J115") (pin "1") (pinfunction "1_1") (pintype "passive"))
      (node (ref "J115") (pin "2") (pinfunction "2_2") (pintype "passive"))
      (node (ref "J116") (pin "1") (pinfunction "1_1") (pintype "passive"))
      (node (ref "J116") (pin "2") (pinfunction "2_2") (pintype "passive"))
      (node (ref "J117") (pin "1") (pinfunction "1_1") (pintype "passive"))
      (node (ref "J117") (pin "2") (pinfunction "2_2") (pintype "passive"))
      (node (ref "J118") (pin "1") (pinfunction "1_1") (pintype "passive"))
      (node (ref "J118") (pin "2") (pinfunction "2_2") (pintype "passive"))
      (node (ref "J119") (pin "1") (pinfunction "1_1") (pintype "passive"))
      (node (ref "J119") (pin "2") (pinfunction "2_2") (pintype "passive"))
      (node (ref "J120") (pin "1") (pinfunction "1_1") (pintype "passive"))
      (node (ref "J120") (pin "2") (pinfunction "2_2") (pintype "passive"))
      (node (ref "J121") (pin "1") (pinfunction "1_1") (pintype "passive"))
      (node (ref "J121") (pin "2") (pinfunction "2_2") (pintype "passive"))
      (node (ref "J122") (pin "1") (pinfunction "1_1") (pintype "passive"))
      (node (ref "J122") (pin "2") (pinfunction "2_2") (pintype "passive"))
      (node (ref "J123") (pin "1") (pinfunction "1_1") (pintype "passive"))
      (node (ref "J123") (pin "2") (pinfunction "2_2") (pintype "passive"))
      (node (ref "J124") (pin "1") (pinfunction "1_1") (pintype "passive"))
      (node (ref "J124") (pin "2") (pinfunction "2_2") (pintype "passive"))
      (node (ref "J125") (pin "1") (pinfunction "1_1") (pintype "passive"))
      (node (ref "J125") (pin "2") (pinfunction "2_2") (pintype "passive"))
      (node (ref "J126") (pin "1") (pinfunction "1_1") (pintype "passive"))
      (node (ref "J126") (pin "2") (pinfunction "2_2") (pintype "passive"))
      (node (ref "J127") (pin "1") (pinfunction "1_1") (pintype "passive"))
      (node (ref "J127") (pin "2") (pinfunction "2_2") (pintype "passive"))
      (node (ref "J128") (pin "1") (pinfunction "1_1") (pintype "passive"))
      (node (ref "J128") (pin "2") (pinfunction "2_2") (pintype "passive"))
      (node (ref "J129") (pin "1") (pinfunction "1_1") (pintype "passive"))
      (node (ref "J129") (pin "2") (pinfunction "2_2") (pintype "passive"))
      (node (ref "J130") (pin "1") (pinfunction "1_1") (pintype "passive"))
      (node (ref "J130") (pin "2") (pinfunction "2_2") (pintype "passive"))
      (node (ref "J131") (pin "1") (pinfunction "1_1") (pintype "passive"))
      (node (ref "J131") (pin "2") (pinfunction "2_2") (pintype "passive"))
      (node (ref "J132") (pin "1") (pinfunction "1_1") (pintype "passive"))
      (node (ref "J132") (pin "2") (pinfunction "2_2") (pintype "passive"))
      (node (ref "J133") (pin "1") (pinfunction "1_1") (pintype "passive"))
      (node (ref "J133") (pin "2") (pinfunction "2_2") (pintype "passive"))
      (node (ref "J134") (pin "1") (pinfunction "1_1") (pintype "passive"))
      (node (ref "J134") (pin "2") (pinfunction "2_2") (pintype "passive"))
      (node (ref "J135") (pin "1") (pinfunction "1_1") (pintype "passive"))
      (node (ref "J135") (pin "2") (pinfunction "2_2") (pintype "passive"))
      (node (ref "J136") (pin "1") (pinfunction "1_1") (pintype "passive"))
      (node (ref "J136") (pin "2") (pinfunction "2_2") (pintype "passive"))
      (node (ref "J137") (pin "1") (pinfunction "1_1") (pintype "passive"))
      (node (ref "J137") (pin "2") (pinfunction "2_2") (pintype "passive"))
      (node (ref "J138") (pin "1") (pinfunction "1_1") (pintype "passive"))
      (node (ref "J138") (pin "2") (pinfunction "2_2") (pintype "passive"))
      (node (ref "J139") (pin "1") (pinfunction "1_1") (pintype "passive"))
      (node (ref "J139") (pin "2") (pinfunction "2_2") (pintype "passive"))
      (node (ref "J140") (pin "1") (pinfunction "1_1") (pintype "passive"))
      (node (ref "J140") (pin "2") (pinfunction "2_2") (pintype "passive"))
      (node (ref "J141") (pin "1") (pinfunction "1_1") (pintype "passive"))
      (node (ref "J141") (pin "2") (pinfunction "2_2") (pintype "passive"))
      (node (ref "J142") (pin "1") (pinfunction "1_1") (pintype "passive"))
      (node (ref "J142") (pin "2") (pinfunction "2_2") (pintype "passive"))
      (node (ref "J143") (pin "1") (pinfunction "1_1") (pintype "passive"))
      (node (ref "J143") (pin "2") (pinfunction "2_2") (pintype "passive"))
      (node (ref "J144") (pin "1") (pinfunction "1_1") (pintype "passive"))
      (node (ref "J144") (pin "2") (pinfunction "2_2") (pintype "passive"))
      (node (ref "J145") (pin "1") (pinfunction "1_1") (pintype "passive"))
      (node (ref "J145") (pin "2") (pinfunction "2_2") (pintype "passive"))
      (node (ref "J146") (pin "1") (pinfunction "1_1") (pintype "passive"))
      (node (ref "J146") (pin "2") (pinfunction "2_2") (pintype "passive"))
      (node (ref "J147") (pin "1") (pinfunction "1_1") (pintype "passive"))
      (node (ref "J147") (pin "2") (pinfunction "2_2") (pintype "passive"))
      (node (ref "J148") (pin "1") (pinfunction "1_1") (pintype "passive"))
      (node (ref "J148") (pin "2") (pinfunction "2_2") (pintype "passive"))
      (node (ref "J149") (pin "1") (pinfunction "1_1") (pintype "passive"))
      (node (ref "J149") (pin "2") (pinfunction "2_2") (pintype "passive"))
      (node (ref "J150") (pin "1") (pinfunction "1_1") (pintype "passive"))
      (node (ref "J150") (pin "2") (pinfunction "2_2") (pintype "passive"))
      (node (ref "J151") (pin "1") (pinfunction "1_1") (pintype "passive"))
      (node (ref "J151") (pin "2") (pinfunction "2_2") (pintype "passive"))
      (node (ref "J152") (pin "1") (pinfunction "1_1") (pintype "passive"))
      (node (ref "J152") (pin "2") (pinfunction "2_2") (pintype "passive"))
      (node (ref "J153") (pin "1") (pinfunction "1_1") (pintype "passive"))
      (node (ref "J153") (pin "2") (pinfunction "2_2") (pintype "passive"))
      (node (ref "J154") (pin "1") (pinfunction "1_1") (pintype "passive"))
      (node (ref "J154") (pin "2") (pinfunction "2_2") (pintype "passive"))
      (node (ref "J155") (pin "1") (pinfunction "1_1") (pintype "passive"))
      (node (ref "J155") (pin "2") (pinfunction "2_2") (pintype "passive"))
      (node (ref "J156") (pin "1") (pinfunction "1_1") (pintype "passive"))
      (node (ref "J156") (pin "2") (pinfunction "2_2") (pintype "passive"))
      (node (ref "J85") (pin "1") (pinfunction "1_1") (pintype "passive"))
      (node (ref "J85") (pin "2") (pinfunction "2_2") (pintype "passive"))
      (node (ref "J86") (pin "1") (pinfunction "1_1") (pintype "passive"))
      (node (ref "J86") (pin "2") (pinfunction "2_2") (pintype "passive"))
      (node (ref "J87") (pin "1") (pinfunction "1_1") (pintype "passive"))
      (node (ref "J87") (pin "2") (pinfunction "2_2") (pintype "passive"))
      (node (ref "J88") (pin "1") (pinfunction "1_1") (pintype "passive"))
      (node (ref "J88") (pin "2") (pinfunction "2_2") (pintype "passive"))
      (node (ref "J89") (pin "1") (pinfunction "1_1") (pintype "passive"))
      (node (ref "J89") (pin "2") (pinfunction "2_2") (pintype "passive"))
      (node (ref "J90") (pin "1") (pinfunction "1_1") (pintype "passive"))
      (node (ref "J90") (pin "2") (pinfunction "2_2") (pintype "passive"))
      (node (ref "J91") (pin "1") (pinfunction "1_1") (pintype "passive"))
      (node (ref "J91") (pin "2") (pinfunction "2_2") (pintype "passive"))
      (node (ref "J92") (pin "1") (pinfunction "1_1") (pintype "passive"))
      (node (ref "J92") (pin "2") (pinfunction "2_2") (pintype "passive"))
      (node (ref "J93") (pin "1") (pinfunction "1_1") (pintype "passive"))
      (node (ref "J93") (pin "2") (pinfunction "2_2") (pintype "passive"))
      (node (ref "J94") (pin "1") (pinfunction "1_1") (pintype "passive"))
      (node (ref "J94") (pin "2") (pinfunction "2_2") (pintype "passive"))
      (node (ref "J95") (pin "1") (pinfunction "1_1") (pintype "passive"))
      (node (ref "J95") (pin "2") (pinfunction "2_2") (pintype "passive"))
      (node (ref "J96") (pin "1") (pinfunction "1_1") (pintype "passive"))
      (node (ref "J96") (pin "2") (pinfunction "2_2") (pintype "passive"))
      (node (ref "J97") (pin "1") (pinfunction "1_1") (pintype "passive"))
      (node (ref "J97") (pin "2") (pinfunction "2_2") (pintype "passive"))
      (node (ref "J98") (pin "1") (pinfunction "1_1") (pintype "passive"))
      (node (ref "J98") (pin "2") (pinfunction "2_2") (pintype "passive"))
      (node (ref "J99") (pin "1") (pinfunction "1_1") (pintype "passive"))
      (node (ref "J99") (pin "2") (pinfunction "2_2") (pintype "passive"))
    )
  )
)
